# rel-alu.net
KiCad netlist of a schematic drawn in EAGLE
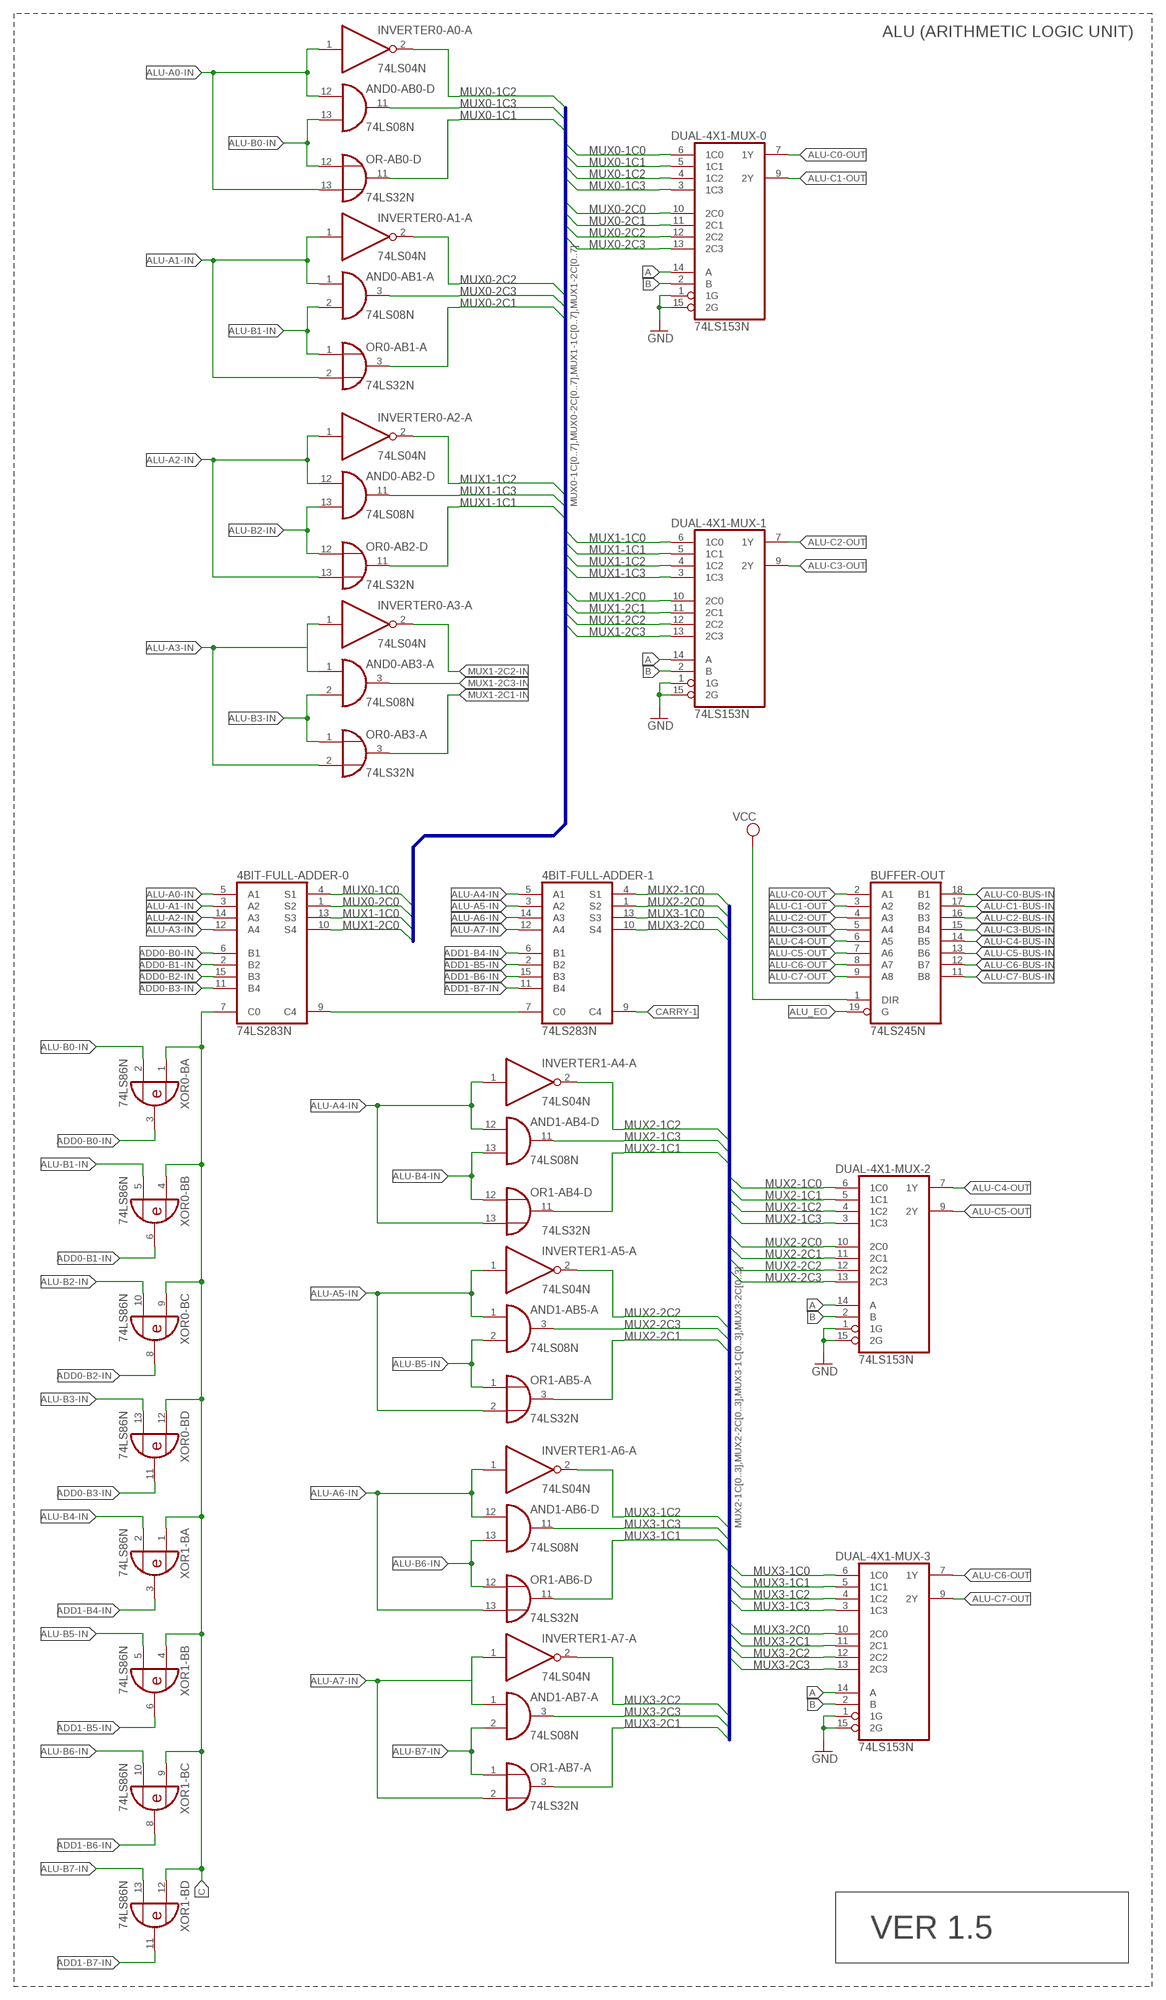
[diagram p0: schematic, sheet 1]

(export (version "E")
  (design (tool "Eeschema 10.0.6"))
  (components
    (comp (ref "4BIT-FULL-ADDER-0")
      (value "74LS283N")
      (footprint "eagle-import:DIL16")
      (libsource (lib "eagle-import") (part "74283NLS"))
    )
    (comp (ref "4BIT-FULL-ADDER-1")
      (value "74LS283N")
      (footprint "eagle-import:DIL16")
      (libsource (lib "eagle-import") (part "74283NLS"))
    )
    (comp (ref "AND0-AB0-")
      (value "74LS08N")
      (footprint "eagle-import:DIL14")
      (libsource (lib "eagle-import") (part "7408NLS"))
    )
    (comp (ref "AND0-AB1-")
      (value "74LS08N")
      (footprint "eagle-import:DIL14")
      (libsource (lib "eagle-import") (part "7408NLS"))
    )
    (comp (ref "AND0-AB2-")
      (value "74LS08N")
      (footprint "eagle-import:DIL14")
      (libsource (lib "eagle-import") (part "7408NLS"))
    )
    (comp (ref "AND0-AB3-")
      (value "74LS08N")
      (footprint "eagle-import:DIL14")
      (libsource (lib "eagle-import") (part "7408NLS"))
    )
    (comp (ref "AND1-AB4-")
      (value "74LS08N")
      (footprint "eagle-import:DIL14")
      (libsource (lib "eagle-import") (part "7408NLS"))
    )
    (comp (ref "AND1-AB5-")
      (value "74LS08N")
      (footprint "eagle-import:DIL14")
      (libsource (lib "eagle-import") (part "7408NLS"))
    )
    (comp (ref "AND1-AB6-")
      (value "74LS08N")
      (footprint "eagle-import:DIL14")
      (libsource (lib "eagle-import") (part "7408NLS"))
    )
    (comp (ref "AND1-AB7-")
      (value "74LS08N")
      (footprint "eagle-import:DIL14")
      (libsource (lib "eagle-import") (part "7408NLS"))
    )
    (comp (ref "BUFFER-OUT")
      (value "74LS245N")
      (footprint "eagle-import:DIL20")
      (libsource (lib "eagle-import") (part "74245NLS"))
    )
    (comp (ref "DUAL-4X1-MUX-0")
      (value "74LS153N")
      (footprint "eagle-import:DIL16")
      (libsource (lib "eagle-import") (part "74153NLS"))
    )
    (comp (ref "DUAL-4X1-MUX-1")
      (value "74LS153N")
      (footprint "eagle-import:DIL16")
      (libsource (lib "eagle-import") (part "74153NLS"))
    )
    (comp (ref "DUAL-4X1-MUX-2")
      (value "74LS153N")
      (footprint "eagle-import:DIL16")
      (libsource (lib "eagle-import") (part "74153NLS"))
    )
    (comp (ref "DUAL-4X1-MUX-3")
      (value "74LS153N")
      (footprint "eagle-import:DIL16")
      (libsource (lib "eagle-import") (part "74153NLS"))
    )
    (comp (ref "INVERTER0-A0-")
      (value "74LS04N")
      (footprint "eagle-import:DIL14")
      (libsource (lib "eagle-import") (part "7404NLS"))
    )
    (comp (ref "INVERTER0-A1-")
      (value "74LS04N")
      (footprint "eagle-import:DIL14")
      (libsource (lib "eagle-import") (part "7404NLS"))
    )
    (comp (ref "INVERTER0-A2-")
      (value "74LS04N")
      (footprint "eagle-import:DIL14")
      (libsource (lib "eagle-import") (part "7404NLS"))
    )
    (comp (ref "INVERTER0-A3-")
      (value "74LS04N")
      (footprint "eagle-import:DIL14")
      (libsource (lib "eagle-import") (part "7404NLS"))
    )
    (comp (ref "INVERTER1-A4-")
      (value "74LS04N")
      (footprint "eagle-import:DIL14")
      (libsource (lib "eagle-import") (part "7404NLS"))
    )
    (comp (ref "INVERTER1-A5-")
      (value "74LS04N")
      (footprint "eagle-import:DIL14")
      (libsource (lib "eagle-import") (part "7404NLS"))
    )
    (comp (ref "INVERTER1-A6-")
      (value "74LS04N")
      (footprint "eagle-import:DIL14")
      (libsource (lib "eagle-import") (part "7404NLS"))
    )
    (comp (ref "INVERTER1-A7-")
      (value "74LS04N")
      (footprint "eagle-import:DIL14")
      (libsource (lib "eagle-import") (part "7404NLS"))
    )
    (comp (ref "OR-AB0-")
      (value "74LS32N")
      (footprint "eagle-import:DIL14")
      (libsource (lib "eagle-import") (part "7432NLS"))
    )
    (comp (ref "OR0-AB1-")
      (value "74LS32N")
      (footprint "eagle-import:DIL14")
      (libsource (lib "eagle-import") (part "7432NLS"))
    )
    (comp (ref "OR0-AB2-")
      (value "74LS32N")
      (footprint "eagle-import:DIL14")
      (libsource (lib "eagle-import") (part "7432NLS"))
    )
    (comp (ref "OR0-AB3-")
      (value "74LS32N")
      (footprint "eagle-import:DIL14")
      (libsource (lib "eagle-import") (part "7432NLS"))
    )
    (comp (ref "OR1-AB4-")
      (value "74LS32N")
      (footprint "eagle-import:DIL14")
      (libsource (lib "eagle-import") (part "7432NLS"))
    )
    (comp (ref "OR1-AB5-")
      (value "74LS32N")
      (footprint "eagle-import:DIL14")
      (libsource (lib "eagle-import") (part "7432NLS"))
    )
    (comp (ref "OR1-AB6-")
      (value "74LS32N")
      (footprint "eagle-import:DIL14")
      (libsource (lib "eagle-import") (part "7432NLS"))
    )
    (comp (ref "OR1-AB7-")
      (value "74LS32N")
      (footprint "eagle-import:DIL14")
      (libsource (lib "eagle-import") (part "7432NLS"))
    )
    (comp (ref "XOR0-B")
      (value "74LS86N")
      (footprint "eagle-import:DIL14")
      (libsource (lib "eagle-import") (part "7486NLS"))
    )
    (comp (ref "XOR1-B")
      (value "74LS86N")
      (footprint "eagle-import:DIL14")
      (libsource (lib "eagle-import") (part "7486NLS"))
    )
  )
  (nets
    (net (code "1") (name "/MUX0-1C0") (class "Default")
      (node (ref "4BIT-FULL-ADDER-0") (pin "4") (pinfunction "S1_4") (pintype "output"))
      (node (ref "DUAL-4X1-MUX-0") (pin "6") (pinfunction "1C0_6") (pintype "input"))
    )
    (net (code "2") (name "/MUX0-1C1") (class "Default")
      (node (ref "DUAL-4X1-MUX-0") (pin "5") (pinfunction "1C1_5") (pintype "input"))
      (node (ref "OR-AB0-") (pin "11") (pinfunction "O_11") (pintype "output"))
    )
    (net (code "3") (name "/MUX0-1C2") (class "Default")
      (node (ref "DUAL-4X1-MUX-0") (pin "4") (pinfunction "1C2_4") (pintype "input"))
      (node (ref "INVERTER0-A0-") (pin "2") (pinfunction "O_2") (pintype "output"))
    )
    (net (code "4") (name "/MUX0-1C3") (class "Default")
      (node (ref "AND0-AB0-") (pin "11") (pinfunction "O_11") (pintype "output"))
      (node (ref "DUAL-4X1-MUX-0") (pin "3") (pinfunction "1C3_3") (pintype "input"))
    )
    (net (code "5") (name "/MUX0-2C0") (class "Default")
      (node (ref "4BIT-FULL-ADDER-0") (pin "1") (pinfunction "S2_1") (pintype "output"))
      (node (ref "DUAL-4X1-MUX-0") (pin "10") (pinfunction "2C0_10") (pintype "input"))
    )
    (net (code "6") (name "/MUX0-2C1") (class "Default")
      (node (ref "DUAL-4X1-MUX-0") (pin "11") (pinfunction "2C1_11") (pintype "input"))
      (node (ref "OR0-AB1-") (pin "3") (pinfunction "O_3") (pintype "output"))
    )
    (net (code "7") (name "/MUX0-2C2") (class "Default")
      (node (ref "DUAL-4X1-MUX-0") (pin "12") (pinfunction "2C2_12") (pintype "input"))
      (node (ref "INVERTER0-A1-") (pin "2") (pinfunction "O_2") (pintype "output"))
    )
    (net (code "8") (name "/MUX0-2C3") (class "Default")
      (node (ref "AND0-AB1-") (pin "3") (pinfunction "O_3") (pintype "output"))
      (node (ref "DUAL-4X1-MUX-0") (pin "13") (pinfunction "2C3_13") (pintype "input"))
    )
    (net (code "9") (name "/MUX1-1C0") (class "Default")
      (node (ref "4BIT-FULL-ADDER-0") (pin "13") (pinfunction "S3_13") (pintype "output"))
      (node (ref "DUAL-4X1-MUX-1") (pin "6") (pinfunction "1C0_6") (pintype "input"))
    )
    (net (code "10") (name "/MUX1-1C1") (class "Default")
      (node (ref "DUAL-4X1-MUX-1") (pin "5") (pinfunction "1C1_5") (pintype "input"))
      (node (ref "OR0-AB2-") (pin "11") (pinfunction "O_11") (pintype "output"))
    )
    (net (code "11") (name "/MUX1-1C2") (class "Default")
      (node (ref "DUAL-4X1-MUX-1") (pin "4") (pinfunction "1C2_4") (pintype "input"))
      (node (ref "INVERTER0-A2-") (pin "2") (pinfunction "O_2") (pintype "output"))
    )
    (net (code "12") (name "/MUX1-1C3") (class "Default")
      (node (ref "AND0-AB2-") (pin "11") (pinfunction "O_11") (pintype "output"))
      (node (ref "DUAL-4X1-MUX-1") (pin "3") (pinfunction "1C3_3") (pintype "input"))
    )
    (net (code "13") (name "/MUX1-2C0") (class "Default")
      (node (ref "4BIT-FULL-ADDER-0") (pin "10") (pinfunction "S4_10") (pintype "output"))
      (node (ref "DUAL-4X1-MUX-1") (pin "10") (pinfunction "2C0_10") (pintype "input"))
    )
    (net (code "14") (name "/MUX1-2C1") (class "Default")
      (node (ref "DUAL-4X1-MUX-1") (pin "11") (pinfunction "2C1_11") (pintype "input"))
    )
    (net (code "15") (name "/MUX1-2C2") (class "Default")
      (node (ref "DUAL-4X1-MUX-1") (pin "12") (pinfunction "2C2_12") (pintype "input"))
    )
    (net (code "16") (name "/MUX1-2C3") (class "Default")
      (node (ref "DUAL-4X1-MUX-1") (pin "13") (pinfunction "2C3_13") (pintype "input"))
    )
    (net (code "17") (name "/MUX2-1C0") (class "Default")
      (node (ref "4BIT-FULL-ADDER-1") (pin "4") (pinfunction "S1_4") (pintype "output"))
      (node (ref "DUAL-4X1-MUX-2") (pin "6") (pinfunction "1C0_6") (pintype "input"))
    )
    (net (code "18") (name "/MUX2-1C1") (class "Default")
      (node (ref "DUAL-4X1-MUX-2") (pin "5") (pinfunction "1C1_5") (pintype "input"))
      (node (ref "OR1-AB4-") (pin "11") (pinfunction "O_11") (pintype "output"))
    )
    (net (code "19") (name "/MUX2-1C2") (class "Default")
      (node (ref "DUAL-4X1-MUX-2") (pin "4") (pinfunction "1C2_4") (pintype "input"))
      (node (ref "INVERTER1-A4-") (pin "2") (pinfunction "O_2") (pintype "output"))
    )
    (net (code "20") (name "/MUX2-1C3") (class "Default")
      (node (ref "AND1-AB4-") (pin "11") (pinfunction "O_11") (pintype "output"))
      (node (ref "DUAL-4X1-MUX-2") (pin "3") (pinfunction "1C3_3") (pintype "input"))
    )
    (net (code "21") (name "/MUX2-2C0") (class "Default")
      (node (ref "4BIT-FULL-ADDER-1") (pin "1") (pinfunction "S2_1") (pintype "output"))
      (node (ref "DUAL-4X1-MUX-2") (pin "10") (pinfunction "2C0_10") (pintype "input"))
    )
    (net (code "22") (name "/MUX2-2C1") (class "Default")
      (node (ref "DUAL-4X1-MUX-2") (pin "11") (pinfunction "2C1_11") (pintype "input"))
      (node (ref "OR1-AB5-") (pin "3") (pinfunction "O_3") (pintype "output"))
    )
    (net (code "23") (name "/MUX2-2C2") (class "Default")
      (node (ref "DUAL-4X1-MUX-2") (pin "12") (pinfunction "2C2_12") (pintype "input"))
      (node (ref "INVERTER1-A5-") (pin "2") (pinfunction "O_2") (pintype "output"))
    )
    (net (code "24") (name "/MUX2-2C3") (class "Default")
      (node (ref "AND1-AB5-") (pin "3") (pinfunction "O_3") (pintype "output"))
      (node (ref "DUAL-4X1-MUX-2") (pin "13") (pinfunction "2C3_13") (pintype "input"))
    )
    (net (code "25") (name "/MUX3-1C0") (class "Default")
      (node (ref "4BIT-FULL-ADDER-1") (pin "13") (pinfunction "S3_13") (pintype "output"))
      (node (ref "DUAL-4X1-MUX-3") (pin "6") (pinfunction "1C0_6") (pintype "input"))
    )
    (net (code "26") (name "/MUX3-1C1") (class "Default")
      (node (ref "DUAL-4X1-MUX-3") (pin "5") (pinfunction "1C1_5") (pintype "input"))
      (node (ref "OR1-AB6-") (pin "11") (pinfunction "O_11") (pintype "output"))
    )
    (net (code "27") (name "/MUX3-1C2") (class "Default")
      (node (ref "DUAL-4X1-MUX-3") (pin "4") (pinfunction "1C2_4") (pintype "input"))
      (node (ref "INVERTER1-A6-") (pin "2") (pinfunction "O_2") (pintype "output"))
    )
    (net (code "28") (name "/MUX3-1C3") (class "Default")
      (node (ref "AND1-AB6-") (pin "11") (pinfunction "O_11") (pintype "output"))
      (node (ref "DUAL-4X1-MUX-3") (pin "3") (pinfunction "1C3_3") (pintype "input"))
    )
    (net (code "29") (name "/MUX3-2C0") (class "Default")
      (node (ref "4BIT-FULL-ADDER-1") (pin "10") (pinfunction "S4_10") (pintype "output"))
      (node (ref "DUAL-4X1-MUX-3") (pin "10") (pinfunction "2C0_10") (pintype "input"))
    )
    (net (code "30") (name "/MUX3-2C1") (class "Default")
      (node (ref "DUAL-4X1-MUX-3") (pin "11") (pinfunction "2C1_11") (pintype "input"))
      (node (ref "OR1-AB7-") (pin "3") (pinfunction "O_3") (pintype "output"))
    )
    (net (code "31") (name "/MUX3-2C2") (class "Default")
      (node (ref "DUAL-4X1-MUX-3") (pin "12") (pinfunction "2C2_12") (pintype "input"))
      (node (ref "INVERTER1-A7-") (pin "2") (pinfunction "O_2") (pintype "output"))
    )
    (net (code "32") (name "/MUX3-2C3") (class "Default")
      (node (ref "AND1-AB7-") (pin "3") (pinfunction "O_3") (pintype "output"))
      (node (ref "DUAL-4X1-MUX-3") (pin "13") (pinfunction "2C3_13") (pintype "input"))
    )
    (net (code "35") (name "A") (class "Default")
      (node (ref "DUAL-4X1-MUX-0") (pin "14") (pinfunction "A_14") (pintype "input"))
      (node (ref "DUAL-4X1-MUX-1") (pin "14") (pinfunction "A_14") (pintype "input"))
      (node (ref "DUAL-4X1-MUX-2") (pin "14") (pinfunction "A_14") (pintype "input"))
      (node (ref "DUAL-4X1-MUX-3") (pin "14") (pinfunction "A_14") (pintype "input"))
    )
    (net (code "36") (name "ADD0-B0-IN") (class "Default")
      (node (ref "4BIT-FULL-ADDER-0") (pin "6") (pinfunction "B1_6") (pintype "input"))
      (node (ref "XOR0-B") (pin "3") (pinfunction "O_3") (pintype "output"))
    )
    (net (code "37") (name "ADD0-B1-IN") (class "Default")
      (node (ref "4BIT-FULL-ADDER-0") (pin "2") (pinfunction "B2_2") (pintype "input"))
      (node (ref "XOR0-B") (pin "6") (pinfunction "O_6") (pintype "output"))
    )
    (net (code "38") (name "ADD0-B2-IN") (class "Default")
      (node (ref "4BIT-FULL-ADDER-0") (pin "15") (pinfunction "B3_15") (pintype "input"))
      (node (ref "XOR0-B") (pin "8") (pinfunction "O_8") (pintype "output"))
    )
    (net (code "39") (name "ADD0-B3-IN") (class "Default")
      (node (ref "4BIT-FULL-ADDER-0") (pin "11") (pinfunction "B4_11") (pintype "input"))
      (node (ref "XOR0-B") (pin "11") (pinfunction "O_11") (pintype "output"))
    )
    (net (code "40") (name "ADD1-B4-IN") (class "Default")
      (node (ref "4BIT-FULL-ADDER-1") (pin "6") (pinfunction "B1_6") (pintype "input"))
      (node (ref "XOR1-B") (pin "3") (pinfunction "O_3") (pintype "output"))
    )
    (net (code "41") (name "ADD1-B5-IN") (class "Default")
      (node (ref "4BIT-FULL-ADDER-1") (pin "2") (pinfunction "B2_2") (pintype "input"))
      (node (ref "XOR1-B") (pin "6") (pinfunction "O_6") (pintype "output"))
    )
    (net (code "42") (name "ADD1-B6-IN") (class "Default")
      (node (ref "4BIT-FULL-ADDER-1") (pin "15") (pinfunction "B3_15") (pintype "input"))
      (node (ref "XOR1-B") (pin "8") (pinfunction "O_8") (pintype "output"))
    )
    (net (code "43") (name "ADD1-B7-IN") (class "Default")
      (node (ref "4BIT-FULL-ADDER-1") (pin "11") (pinfunction "B4_11") (pintype "input"))
      (node (ref "XOR1-B") (pin "11") (pinfunction "O_11") (pintype "output"))
    )
    (net (code "44") (name "ALU-A0-IN") (class "Default")
      (node (ref "4BIT-FULL-ADDER-0") (pin "5") (pinfunction "A1_5") (pintype "input"))
      (node (ref "AND0-AB0-") (pin "12") (pinfunction "I0_12") (pintype "input"))
      (node (ref "INVERTER0-A0-") (pin "1") (pinfunction "I_1") (pintype "input"))
      (node (ref "OR-AB0-") (pin "13") (pinfunction "I1_13") (pintype "input"))
    )
    (net (code "45") (name "ALU-A1-IN") (class "Default")
      (node (ref "4BIT-FULL-ADDER-0") (pin "3") (pinfunction "A2_3") (pintype "input"))
      (node (ref "AND0-AB1-") (pin "1") (pinfunction "I0_1") (pintype "input"))
      (node (ref "INVERTER0-A1-") (pin "1") (pinfunction "I_1") (pintype "input"))
      (node (ref "OR0-AB1-") (pin "2") (pinfunction "I1_2") (pintype "input"))
    )
    (net (code "46") (name "ALU-A2-IN") (class "Default")
      (node (ref "4BIT-FULL-ADDER-0") (pin "14") (pinfunction "A3_14") (pintype "input"))
      (node (ref "AND0-AB2-") (pin "12") (pinfunction "I0_12") (pintype "input"))
      (node (ref "INVERTER0-A2-") (pin "1") (pinfunction "I_1") (pintype "input"))
      (node (ref "OR0-AB2-") (pin "13") (pinfunction "I1_13") (pintype "input"))
    )
    (net (code "47") (name "ALU-A3-IN") (class "Default")
      (node (ref "4BIT-FULL-ADDER-0") (pin "12") (pinfunction "A4_12") (pintype "input"))
      (node (ref "AND0-AB3-") (pin "1") (pinfunction "I0_1") (pintype "input"))
      (node (ref "INVERTER0-A3-") (pin "1") (pinfunction "I_1") (pintype "input"))
      (node (ref "OR0-AB3-") (pin "2") (pinfunction "I1_2") (pintype "input"))
    )
    (net (code "48") (name "ALU-A4-IN") (class "Default")
      (node (ref "4BIT-FULL-ADDER-1") (pin "5") (pinfunction "A1_5") (pintype "input"))
      (node (ref "AND1-AB4-") (pin "12") (pinfunction "I0_12") (pintype "input"))
      (node (ref "INVERTER1-A4-") (pin "1") (pinfunction "I_1") (pintype "input"))
      (node (ref "OR1-AB4-") (pin "13") (pinfunction "I1_13") (pintype "input"))
    )
    (net (code "49") (name "ALU-A5-IN") (class "Default")
      (node (ref "4BIT-FULL-ADDER-1") (pin "3") (pinfunction "A2_3") (pintype "input"))
      (node (ref "AND1-AB5-") (pin "1") (pinfunction "I0_1") (pintype "input"))
      (node (ref "INVERTER1-A5-") (pin "1") (pinfunction "I_1") (pintype "input"))
      (node (ref "OR1-AB5-") (pin "2") (pinfunction "I1_2") (pintype "input"))
    )
    (net (code "50") (name "ALU-A6-IN") (class "Default")
      (node (ref "4BIT-FULL-ADDER-1") (pin "14") (pinfunction "A3_14") (pintype "input"))
      (node (ref "AND1-AB6-") (pin "12") (pinfunction "I0_12") (pintype "input"))
      (node (ref "INVERTER1-A6-") (pin "1") (pinfunction "I_1") (pintype "input"))
      (node (ref "OR1-AB6-") (pin "13") (pinfunction "I1_13") (pintype "input"))
    )
    (net (code "51") (name "ALU-A7-IN") (class "Default")
      (node (ref "4BIT-FULL-ADDER-1") (pin "12") (pinfunction "A4_12") (pintype "input"))
      (node (ref "AND1-AB7-") (pin "1") (pinfunction "I0_1") (pintype "input"))
      (node (ref "INVERTER1-A7-") (pin "1") (pinfunction "I_1") (pintype "input"))
      (node (ref "OR1-AB7-") (pin "2") (pinfunction "I1_2") (pintype "input"))
    )
    (net (code "52") (name "ALU-B0-IN") (class "Default")
      (node (ref "AND0-AB0-") (pin "13") (pinfunction "I1_13") (pintype "input"))
      (node (ref "OR-AB0-") (pin "12") (pinfunction "I0_12") (pintype "input"))
      (node (ref "XOR0-B") (pin "2") (pinfunction "I1_2") (pintype "input"))
    )
    (net (code "53") (name "ALU-B1-IN") (class "Default")
      (node (ref "AND0-AB1-") (pin "2") (pinfunction "I1_2") (pintype "input"))
      (node (ref "OR0-AB1-") (pin "1") (pinfunction "I0_1") (pintype "input"))
      (node (ref "XOR0-B") (pin "5") (pinfunction "I1_5") (pintype "input"))
    )
    (net (code "54") (name "ALU-B2-IN") (class "Default")
      (node (ref "AND0-AB2-") (pin "13") (pinfunction "I1_13") (pintype "input"))
      (node (ref "OR0-AB2-") (pin "12") (pinfunction "I0_12") (pintype "input"))
      (node (ref "XOR0-B") (pin "10") (pinfunction "I1_10") (pintype "input"))
    )
    (net (code "55") (name "ALU-B3-IN") (class "Default")
      (node (ref "AND0-AB3-") (pin "2") (pinfunction "I1_2") (pintype "input"))
      (node (ref "OR0-AB3-") (pin "1") (pinfunction "I0_1") (pintype "input"))
      (node (ref "XOR0-B") (pin "13") (pinfunction "I1_13") (pintype "input"))
    )
    (net (code "56") (name "ALU-B4-IN") (class "Default")
      (node (ref "AND1-AB4-") (pin "13") (pinfunction "I1_13") (pintype "input"))
      (node (ref "OR1-AB4-") (pin "12") (pinfunction "I0_12") (pintype "input"))
      (node (ref "XOR1-B") (pin "2") (pinfunction "I1_2") (pintype "input"))
    )
    (net (code "57") (name "ALU-B5-IN") (class "Default")
      (node (ref "AND1-AB5-") (pin "2") (pinfunction "I1_2") (pintype "input"))
      (node (ref "OR1-AB5-") (pin "1") (pinfunction "I0_1") (pintype "input"))
      (node (ref "XOR1-B") (pin "5") (pinfunction "I1_5") (pintype "input"))
    )
    (net (code "58") (name "ALU-B6-IN") (class "Default")
      (node (ref "AND1-AB6-") (pin "13") (pinfunction "I1_13") (pintype "input"))
      (node (ref "OR1-AB6-") (pin "12") (pinfunction "I0_12") (pintype "input"))
      (node (ref "XOR1-B") (pin "10") (pinfunction "I1_10") (pintype "input"))
    )
    (net (code "59") (name "ALU-B7-IN") (class "Default")
      (node (ref "AND1-AB7-") (pin "2") (pinfunction "I1_2") (pintype "input"))
      (node (ref "OR1-AB7-") (pin "1") (pinfunction "I0_1") (pintype "input"))
      (node (ref "XOR1-B") (pin "13") (pinfunction "I1_13") (pintype "input"))
    )
    (net (code "60") (name "ALU-C0-BUS-IN") (class "Default")
      (node (ref "BUFFER-OUT") (pin "18") (pinfunction "B1_18") (pintype "bidirectional"))
    )
    (net (code "61") (name "ALU-C0-OUT") (class "Default")
      (node (ref "BUFFER-OUT") (pin "2") (pinfunction "A1_2") (pintype "bidirectional"))
      (node (ref "DUAL-4X1-MUX-0") (pin "7") (pinfunction "1Y_7") (pintype "output"))
    )
    (net (code "62") (name "ALU-C1-BUS-IN") (class "Default")
      (node (ref "BUFFER-OUT") (pin "17") (pinfunction "B2_17") (pintype "bidirectional"))
    )
    (net (code "63") (name "ALU-C1-OUT") (class "Default")
      (node (ref "BUFFER-OUT") (pin "3") (pinfunction "A2_3") (pintype "bidirectional"))
      (node (ref "DUAL-4X1-MUX-0") (pin "9") (pinfunction "2Y_9") (pintype "output"))
    )
    (net (code "64") (name "ALU-C2-BUS-IN") (class "Default")
      (node (ref "BUFFER-OUT") (pin "16") (pinfunction "B3_16") (pintype "bidirectional"))
    )
    (net (code "65") (name "ALU-C2-OUT") (class "Default")
      (node (ref "BUFFER-OUT") (pin "4") (pinfunction "A3_4") (pintype "bidirectional"))
      (node (ref "DUAL-4X1-MUX-1") (pin "7") (pinfunction "1Y_7") (pintype "output"))
    )
    (net (code "66") (name "ALU-C3-BUS-IN") (class "Default")
      (node (ref "BUFFER-OUT") (pin "15") (pinfunction "B4_15") (pintype "bidirectional"))
    )
    (net (code "67") (name "ALU-C3-OUT") (class "Default")
      (node (ref "BUFFER-OUT") (pin "5") (pinfunction "A4_5") (pintype "bidirectional"))
      (node (ref "DUAL-4X1-MUX-1") (pin "9") (pinfunction "2Y_9") (pintype "output"))
    )
    (net (code "68") (name "ALU-C4-BUS-IN") (class "Default")
      (node (ref "BUFFER-OUT") (pin "14") (pinfunction "B5_14") (pintype "bidirectional"))
    )
    (net (code "69") (name "ALU-C4-OUT") (class "Default")
      (node (ref "BUFFER-OUT") (pin "6") (pinfunction "A5_6") (pintype "bidirectional"))
      (node (ref "DUAL-4X1-MUX-2") (pin "7") (pinfunction "1Y_7") (pintype "output"))
    )
    (net (code "70") (name "ALU-C5-BUS-IN") (class "Default")
      (node (ref "BUFFER-OUT") (pin "13") (pinfunction "B6_13") (pintype "bidirectional"))
    )
    (net (code "71") (name "ALU-C5-OUT") (class "Default")
      (node (ref "BUFFER-OUT") (pin "7") (pinfunction "A6_7") (pintype "bidirectional"))
      (node (ref "DUAL-4X1-MUX-2") (pin "9") (pinfunction "2Y_9") (pintype "output"))
    )
    (net (code "72") (name "ALU-C6-BUS-IN") (class "Default")
      (node (ref "BUFFER-OUT") (pin "12") (pinfunction "B7_12") (pintype "bidirectional"))
    )
    (net (code "73") (name "ALU-C6-OUT") (class "Default")
      (node (ref "BUFFER-OUT") (pin "8") (pinfunction "A7_8") (pintype "bidirectional"))
      (node (ref "DUAL-4X1-MUX-3") (pin "7") (pinfunction "1Y_7") (pintype "output"))
    )
    (net (code "74") (name "ALU-C7-BUS-IN") (class "Default")
      (node (ref "BUFFER-OUT") (pin "11") (pinfunction "B8_11") (pintype "bidirectional"))
    )
    (net (code "75") (name "ALU-C7-OUT") (class "Default")
      (node (ref "BUFFER-OUT") (pin "9") (pinfunction "A8_9") (pintype "bidirectional"))
      (node (ref "DUAL-4X1-MUX-3") (pin "9") (pinfunction "2Y_9") (pintype "output"))
    )
    (net (code "76") (name "ALU_EO") (class "Default")
      (node (ref "BUFFER-OUT") (pin "19") (pinfunction "G_19") (pintype "input"))
    )
    (net (code "77") (name "B") (class "Default")
      (node (ref "DUAL-4X1-MUX-0") (pin "2") (pinfunction "B_2") (pintype "input"))
      (node (ref "DUAL-4X1-MUX-1") (pin "2") (pinfunction "B_2") (pintype "input"))
      (node (ref "DUAL-4X1-MUX-2") (pin "2") (pinfunction "B_2") (pintype "input"))
      (node (ref "DUAL-4X1-MUX-3") (pin "2") (pinfunction "B_2") (pintype "input"))
    )
    (net (code "78") (name "C") (class "Default")
      (node (ref "4BIT-FULL-ADDER-0") (pin "7") (pinfunction "C0_7") (pintype "input"))
      (node (ref "XOR0-B") (pin "1") (pinfunction "I0_1") (pintype "input"))
      (node (ref "XOR0-B") (pin "12") (pinfunction "I0_12") (pintype "input"))
      (node (ref "XOR0-B") (pin "4") (pinfunction "I0_4") (pintype "input"))
      (node (ref "XOR0-B") (pin "9") (pinfunction "I0_9") (pintype "input"))
      (node (ref "XOR1-B") (pin "1") (pinfunction "I0_1") (pintype "input"))
      (node (ref "XOR1-B") (pin "12") (pinfunction "I0_12") (pintype "input"))
      (node (ref "XOR1-B") (pin "4") (pinfunction "I0_4") (pintype "input"))
      (node (ref "XOR1-B") (pin "9") (pinfunction "I0_9") (pintype "input"))
    )
    (net (code "79") (name "CARRY-1") (class "Default")
      (node (ref "4BIT-FULL-ADDER-1") (pin "9") (pinfunction "C4_9") (pintype "output"))
    )
    (net (code "80") (name "GND") (class "Default")
      (node (ref "DUAL-4X1-MUX-0") (pin "1") (pinfunction "1G_1") (pintype "input"))
      (node (ref "DUAL-4X1-MUX-0") (pin "15") (pinfunction "2G_15") (pintype "input"))
      (node (ref "DUAL-4X1-MUX-1") (pin "1") (pinfunction "1G_1") (pintype "input"))
      (node (ref "DUAL-4X1-MUX-1") (pin "15") (pinfunction "2G_15") (pintype "input"))
      (node (ref "DUAL-4X1-MUX-2") (pin "1") (pinfunction "1G_1") (pintype "input"))
      (node (ref "DUAL-4X1-MUX-2") (pin "15") (pinfunction "2G_15") (pintype "input"))
      (node (ref "DUAL-4X1-MUX-3") (pin "1") (pinfunction "1G_1") (pintype "input"))
      (node (ref "DUAL-4X1-MUX-3") (pin "15") (pinfunction "2G_15") (pintype "input"))
    )
    (net (code "81") (name "MUX1-2C1-IN") (class "Default")
      (node (ref "OR0-AB3-") (pin "3") (pinfunction "O_3") (pintype "output"))
    )
    (net (code "82") (name "MUX1-2C2-IN") (class "Default")
      (node (ref "INVERTER0-A3-") (pin "2") (pinfunction "O_2") (pintype "output"))
    )
    (net (code "83") (name "MUX1-2C3-IN") (class "Default")
      (node (ref "AND0-AB3-") (pin "3") (pinfunction "O_3") (pintype "output"))
    )
    (net (code "84") (name "Net-(4BIT-FULL-ADDER-0A-C4)") (class "Default")
      (node (ref "4BIT-FULL-ADDER-0") (pin "9") (pinfunction "C4_9") (pintype "output"))
      (node (ref "4BIT-FULL-ADDER-1") (pin "7") (pinfunction "C0_7") (pintype "input"))
    )
    (net (code "85") (name "VCC") (class "Default")
      (node (ref "BUFFER-OUT") (pin "1") (pinfunction "DIR_1") (pintype "input"))
    )
  )
)
